# Main.net
KiCad netlist of a schematic drawn in EAGLE
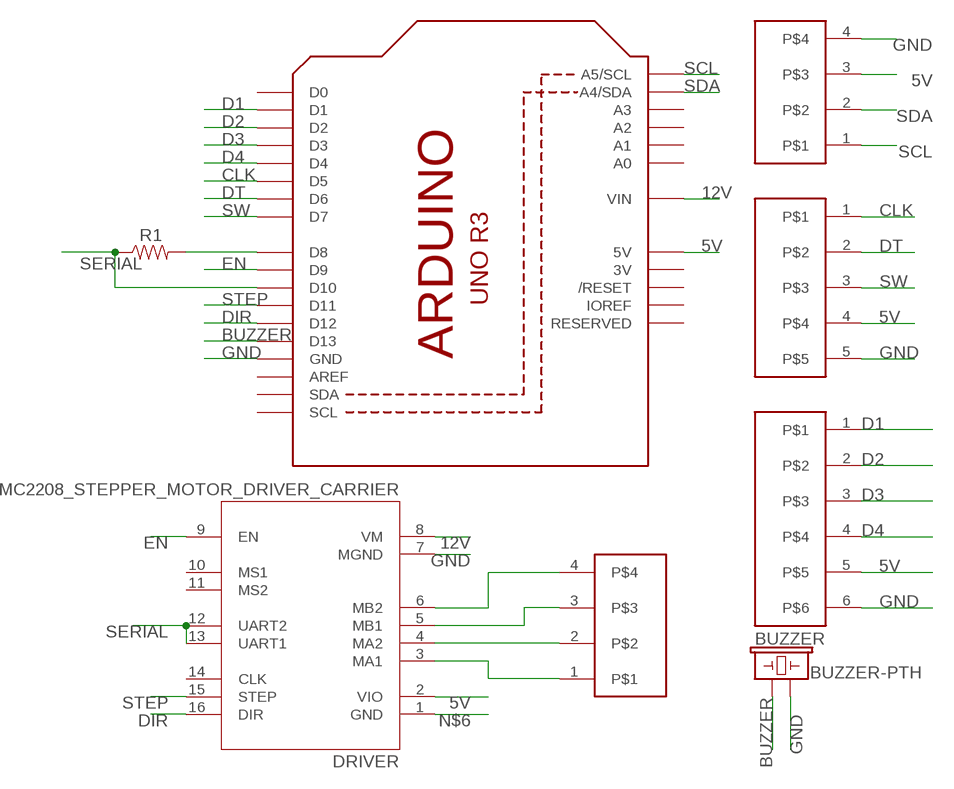
[diagram p0: schematic, sheet 1]

(export (version "E")
  (design (tool "Eeschema 10.0.6"))
  (components
    (comp (ref "BUZZER")
      (value "BUZZER-PTH")
      (footprint "eagle-import:BUZZER-12MM")
      (libsource (lib "eagle-import") (part "BUZZER-PTH"))
    )
    (comp (ref "DISPLAY")
      (value "JST-XH-04-PIN-LONG-PAD")
      (footprint "eagle-import:JST-XH-04-PACKAGE-LONG-PAD")
      (libsource (lib "eagle-import") (part "JST-XH-04-PIN-LONG-PAD"))
    )
    (comp (ref "DRIVER")
      (value "IC_TMC2208_STEPPER_MOTOR_DRIVER_CARRIER")
      (footprint "eagle-import:IC_TMC2208_STEPPER_MOTOR_DRIVER_CARRIER")
      (fields (field (name "MF") "Pololu") (field (name "MP") "DRV8825 STEPPER MOTOR DRIVER CARRIER"))
      (libsource (lib "eagle-import") (part "IC_TMC2208_STEPPER_MOTOR_DRIVER_CARRIER"))
    )
    (comp (ref "ENCODER")
      (value "JST-XH-05-PIN-LONG-PAD")
      (footprint "eagle-import:JST-XH-05-PACKAGE-LONG-PAD")
      (libsource (lib "eagle-import") (part "JST-XH-05-PIN-LONG-PAD"))
    )
    (comp (ref "MOTOR")
      (value "JST-XH-04-PIN-LONG-PAD")
      (footprint "eagle-import:JST-XH-04-PACKAGE-LONG-PAD")
      (libsource (lib "eagle-import") (part "JST-XH-04-PIN-LONG-PAD"))
    )
    (comp (ref "OUTPUT")
      (value "JST-XH-06-PIN-LONG-PAD")
      (footprint "eagle-import:JST-XH-06-PACKAGE-LONG-PAD")
      (libsource (lib "eagle-import") (part "JST-XH-06-PIN-LONG-PAD"))
    )
    (comp (ref "R1")
      (value "RESISTORAXIAL-0.3")
      (footprint "eagle-import:AXIAL-0.3")
      (libsource (lib "eagle-import") (part "RESISTORAXIAL-0.3"))
    )
    (comp (ref "U2")
      (value "ARDUINOR3-BPLACE")
      (footprint "eagle-import:ARDUINOR3-BPLACE")
      (libsource (lib "eagle-import") (part "ARDUINOR3-BPLACE"))
    )
  )
  (nets
    (net (code "1") (name "/3V") (class "Default")
      (node (ref "U2") (pin "3V") (pinfunction "3V_3V") (pintype "power_in"))
    )
    (net (code "2") (name "/5V") (class "Default")
      (node (ref "DISPLAY") (pin "3") (pinfunction "P$3_3") (pintype "bidirectional"))
      (node (ref "DRIVER") (pin "2") (pinfunction "VIO_2") (pintype "power_in"))
      (node (ref "ENCODER") (pin "4") (pinfunction "P$4_4") (pintype "bidirectional"))
      (node (ref "OUTPUT") (pin "5") (pinfunction "P$5_5") (pintype "bidirectional"))
      (node (ref "U2") (pin "5V") (pinfunction "5V_5V") (pintype "power_in"))
    )
    (net (code "3") (name "/12V") (class "Default")
      (node (ref "DRIVER") (pin "8") (pinfunction "VM_8") (pintype "input"))
      (node (ref "U2") (pin "VIN") (pinfunction "VIN_VIN") (pintype "power_in"))
    )
    (net (code "4") (name "/BUZZER") (class "Default")
      (node (ref "BUZZER") (pin "+") (pinfunction "1_+") (pintype "passive"))
      (node (ref "U2") (pin "D13") (pinfunction "D13_D13") (pintype "bidirectional"))
    )
    (net (code "5") (name "/CLK") (class "Default")
      (node (ref "ENCODER") (pin "1") (pinfunction "P$1_1") (pintype "bidirectional"))
      (node (ref "U2") (pin "D5") (pinfunction "D5_D5") (pintype "bidirectional"))
    )
    (net (code "6") (name "/D1") (class "Default")
      (node (ref "OUTPUT") (pin "1") (pinfunction "P$1_1") (pintype "bidirectional"))
      (node (ref "U2") (pin "D1") (pinfunction "D1_D1") (pintype "bidirectional"))
    )
    (net (code "7") (name "/D2") (class "Default")
      (node (ref "OUTPUT") (pin "2") (pinfunction "P$2_2") (pintype "bidirectional"))
      (node (ref "U2") (pin "D2") (pinfunction "D2_D2") (pintype "bidirectional"))
    )
    (net (code "8") (name "/D3") (class "Default")
      (node (ref "OUTPUT") (pin "3") (pinfunction "P$3_3") (pintype "bidirectional"))
      (node (ref "U2") (pin "D3") (pinfunction "D3_D3") (pintype "bidirectional"))
    )
    (net (code "9") (name "/D4") (class "Default")
      (node (ref "OUTPUT") (pin "4") (pinfunction "P$4_4") (pintype "bidirectional"))
      (node (ref "U2") (pin "D4") (pinfunction "D4_D4") (pintype "bidirectional"))
    )
    (net (code "10") (name "/DIR") (class "Default")
      (node (ref "DRIVER") (pin "16") (pinfunction "DIR_16") (pintype "output"))
      (node (ref "U2") (pin "D12") (pinfunction "D12_D12") (pintype "bidirectional"))
    )
    (net (code "11") (name "/DT") (class "Default")
      (node (ref "ENCODER") (pin "2") (pinfunction "P$2_2") (pintype "bidirectional"))
      (node (ref "U2") (pin "D6") (pinfunction "D6_D6") (pintype "bidirectional"))
    )
    (net (code "12") (name "/EN") (class "Default")
      (node (ref "DRIVER") (pin "9") (pinfunction "EN_9") (pintype "input"))
      (node (ref "U2") (pin "D9") (pinfunction "D9_D9") (pintype "bidirectional"))
    )
    (net (code "13") (name "/GND") (class "Default")
      (node (ref "BUZZER") (pin "-") (pinfunction "2_-") (pintype "passive"))
      (node (ref "DISPLAY") (pin "4") (pinfunction "P$4_4") (pintype "bidirectional"))
      (node (ref "DRIVER") (pin "7") (pinfunction "MGND_7") (pintype "input"))
      (node (ref "ENCODER") (pin "5") (pinfunction "P$5_5") (pintype "bidirectional"))
      (node (ref "OUTPUT") (pin "6") (pinfunction "P$6_6") (pintype "bidirectional"))
      (node (ref "U2") (pin "GND") (pinfunction "GND_GND") (pintype "power_in"))
      (node (ref "U2") (pin "GND1") (pinfunction "GND_GND1") (pintype "power_in"))
      (node (ref "U2") (pin "GND2") (pinfunction "GND_GND2") (pintype "power_in"))
    )
    (net (code "14") (name "/N$6") (class "Default")
      (node (ref "DRIVER") (pin "1") (pinfunction "GND_1") (pintype "power_in"))
    )
    (net (code "15") (name "/SCL") (class "Default")
      (node (ref "DISPLAY") (pin "1") (pinfunction "P$1_1") (pintype "bidirectional"))
      (node (ref "U2") (pin "A5") (pinfunction "A5/SCL_A5") (pintype "bidirectional"))
    )
    (net (code "16") (name "/SDA") (class "Default")
      (node (ref "DISPLAY") (pin "2") (pinfunction "P$2_2") (pintype "bidirectional"))
      (node (ref "U2") (pin "A4") (pinfunction "A4/SDA_A4") (pintype "bidirectional"))
    )
    (net (code "17") (name "/SERIAL") (class "Default")
      (node (ref "DRIVER") (pin "12") (pinfunction "UART2_12") (pintype "input"))
      (node (ref "DRIVER") (pin "13") (pinfunction "UART1_13") (pintype "input"))
      (node (ref "R1") (pin "P$1") (pinfunction "1_P$1") (pintype "passive"))
      (node (ref "U2") (pin "D10") (pinfunction "D10_D10") (pintype "bidirectional"))
    )
    (net (code "18") (name "/STEP") (class "Default")
      (node (ref "DRIVER") (pin "15") (pinfunction "STEP_15") (pintype "output"))
      (node (ref "U2") (pin "D11") (pinfunction "D11_D11") (pintype "bidirectional"))
    )
    (net (code "19") (name "/SW") (class "Default")
      (node (ref "ENCODER") (pin "3") (pinfunction "P$3_3") (pintype "bidirectional"))
      (node (ref "U2") (pin "D7") (pinfunction "D7_D7") (pintype "bidirectional"))
    )
    (net (code "20") (name "Net-(DRIVER-MA1)") (class "Default")
      (node (ref "DRIVER") (pin "3") (pinfunction "MA1_3") (pintype "output"))
      (node (ref "MOTOR") (pin "1") (pinfunction "P$1_1") (pintype "bidirectional"))
    )
    (net (code "21") (name "Net-(DRIVER-MA2)") (class "Default")
      (node (ref "DRIVER") (pin "4") (pinfunction "MA2_4") (pintype "output"))
      (node (ref "MOTOR") (pin "2") (pinfunction "P$2_2") (pintype "bidirectional"))
    )
    (net (code "22") (name "Net-(DRIVER-MB1)") (class "Default")
      (node (ref "DRIVER") (pin "5") (pinfunction "MB1_5") (pintype "output"))
      (node (ref "MOTOR") (pin "3") (pinfunction "P$3_3") (pintype "bidirectional"))
    )
    (net (code "23") (name "Net-(DRIVER-MB2)") (class "Default")
      (node (ref "DRIVER") (pin "6") (pinfunction "MB2_6") (pintype "output"))
      (node (ref "MOTOR") (pin "4") (pinfunction "P$4_4") (pintype "bidirectional"))
    )
    (net (code "24") (name "Net-(R1-2)") (class "Default")
      (node (ref "R1") (pin "P$2") (pinfunction "2_P$2") (pintype "passive"))
      (node (ref "U2") (pin "D8") (pinfunction "D8_D8") (pintype "bidirectional"))
    )
    (net (code "25") (name "unconnected-(DRIVER-CLK-Pad14)") (class "Default")
      (node (ref "DRIVER") (pin "14") (pinfunction "CLK_14") (pintype "input"))
    )
    (net (code "26") (name "unconnected-(DRIVER-MS1-Pad10)") (class "Default")
      (node (ref "DRIVER") (pin "10") (pinfunction "MS1_10") (pintype "input"))
    )
    (net (code "27") (name "unconnected-(DRIVER-MS2-Pad11)") (class "Default")
      (node (ref "DRIVER") (pin "11") (pinfunction "MS2_11") (pintype "input"))
    )
    (net (code "28") (name "unconnected-(U2-PadA0)") (class "Default")
      (node (ref "U2") (pin "A0") (pinfunction "A0_A0") (pintype "bidirectional"))
    )
    (net (code "29") (name "unconnected-(U2-PadA1)") (class "Default")
      (node (ref "U2") (pin "A1") (pinfunction "A1_A1") (pintype "bidirectional"))
    )
    (net (code "30") (name "unconnected-(U2-PadA2)") (class "Default")
      (node (ref "U2") (pin "A2") (pinfunction "A2_A2") (pintype "bidirectional"))
    )
    (net (code "31") (name "unconnected-(U2-PadA3)") (class "Default")
      (node (ref "U2") (pin "A3") (pinfunction "A3_A3") (pintype "bidirectional"))
    )
    (net (code "32") (name "unconnected-(U2-PadAREF)") (class "Default")
      (node (ref "U2") (pin "AREF") (pinfunction "AREF_AREF") (pintype "bidirectional"))
    )
    (net (code "33") (name "unconnected-(U2-PadD0)") (class "Default")
      (node (ref "U2") (pin "D0") (pinfunction "D0_D0") (pintype "bidirectional"))
    )
    (net (code "34") (name "unconnected-(U2-PadIOREF)") (class "Default")
      (node (ref "U2") (pin "IOREF") (pinfunction "IOREF_IOREF") (pintype "output"))
    )
    (net (code "35") (name "unconnected-(U2-PadRESERVED)") (class "Default")
      (node (ref "U2") (pin "RESERVED") (pinfunction "RESERVED_RESERVED") (pintype "no_connect"))
    )
    (net (code "36") (name "unconnected-(U2-PadSCL)") (class "Default")
      (node (ref "U2") (pin "SCL") (pinfunction "SCL_SCL") (pintype "bidirectional"))
    )
    (net (code "37") (name "unconnected-(U2-PadSDA)") (class "Default")
      (node (ref "U2") (pin "SDA") (pinfunction "SDA_SDA") (pintype "bidirectional"))
    )
    (net (code "38") (name "unconnected-(U2-{slash}RESET-PadRESET)") (class "Default")
      (node (ref "U2") (pin "RESET") (pinfunction "/RESET_RESET") (pintype "bidirectional"))
    )
  )
)
